# design.net
KiCad netlist of a schematic drawn in Altium Designer
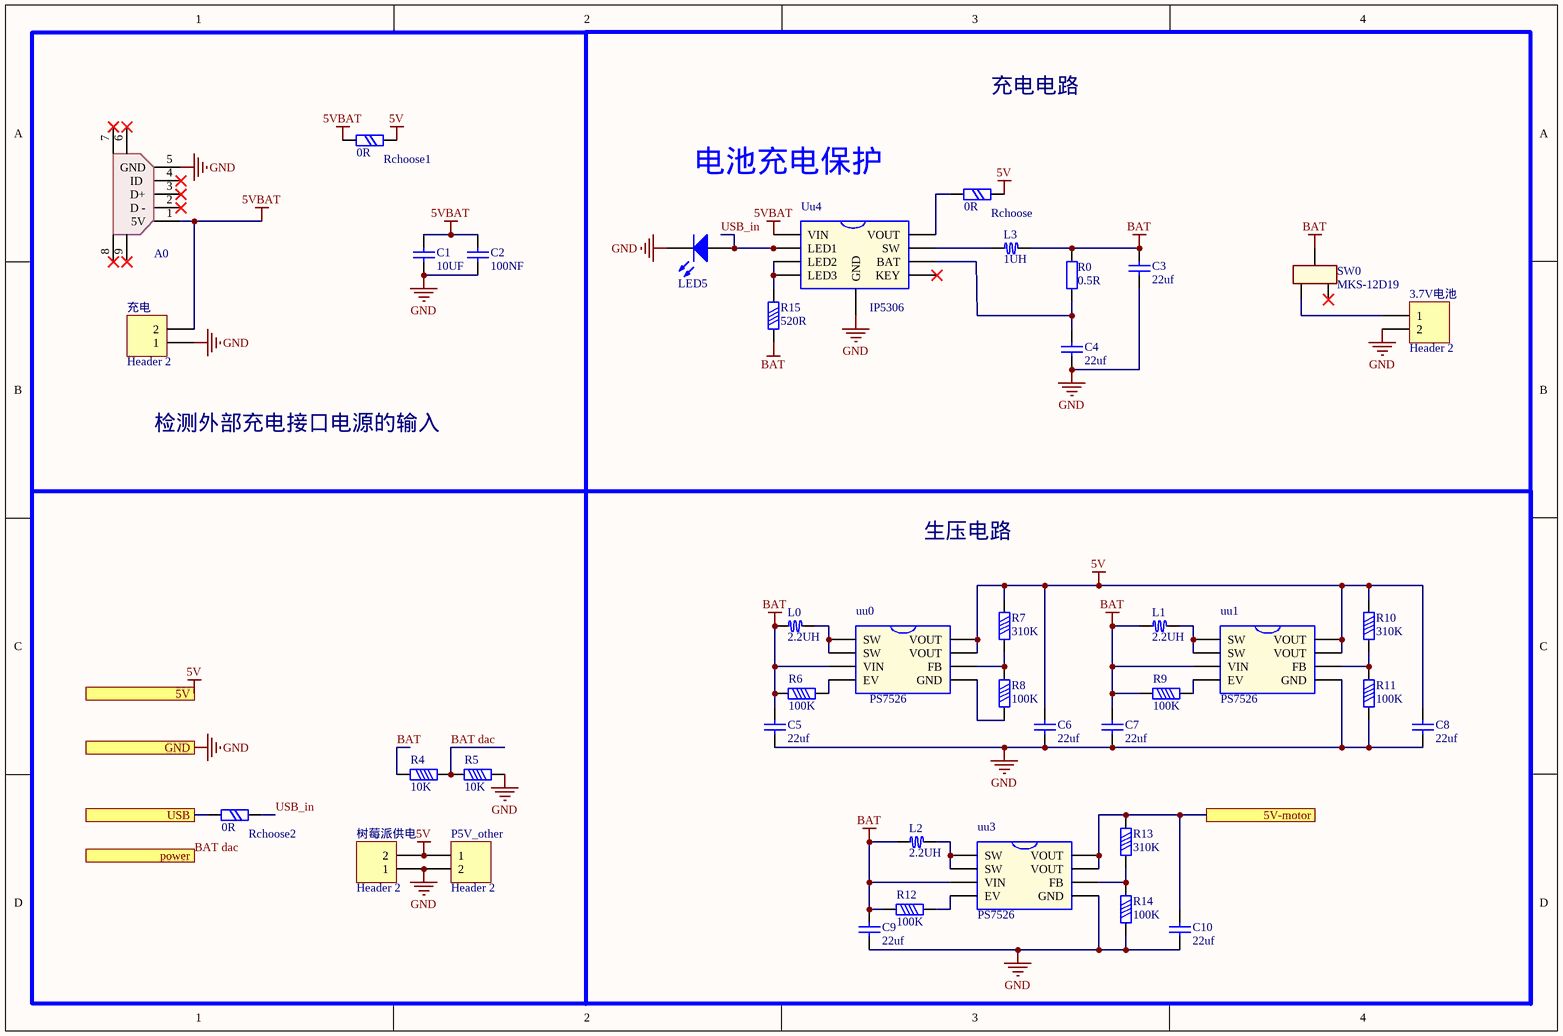
[diagram p0: 电源设计.SchDoc]

(export (version "E")
  (design (tool "Eeschema 10.0.6"))
  (components
    (comp (ref "3.7V电池")
      (value "Header 2")
      (footprint "HX2.54-2")
      (description "Header, 2-Pin")
      (fields (field (name "PUBLISHER") "Altium Limited"))
      (libsource (lib "") (part "Header 2_1"))
    )
    (comp (ref "A0")
      (value "Micro USB")
      (footprint "Micro USB")
      (libsource (lib "tianxiaohua_Schlib") (part "Micro USB"))
    )
    (comp (ref "C1")
      (value "10UF")
      (footprint "CC2012-0805")
      (description "Polarized Capacitor (Radial)")
      (fields (field (name "Comment") "Cap Chip 0805") (field (name "PUBLISHER") "Altium Limited"))
      (libsource (lib "EButterflyIntegratedLibrary") (part "Cap Chip 0805"))
    )
    (comp (ref "C2")
      (value "100NF")
      (footprint "CC2012-0805")
      (description "Polarized Capacitor (Radial)")
      (fields (field (name "Comment") "Cap Chip 0805") (field (name "PUBLISHER") "Altium Limited"))
      (libsource (lib "EButterflyIntegratedLibrary") (part "Cap Chip 0805"))
    )
    (comp (ref "C3")
      (value "22uf")
      (footprint "CC2012-0805")
      (description "Polarized Capacitor (Radial)")
      (fields (field (name "Comment") "Cap Chip 0805") (field (name "PUBLISHER") "Altium Limited"))
      (libsource (lib "EButterflyIntegratedLibrary") (part "Cap Chip 0805"))
    )
    (comp (ref "C4")
      (value "22uf")
      (footprint "CC2012-0805")
      (description "Polarized Capacitor (Radial)")
      (fields (field (name "Comment") "Cap Chip 0805") (field (name "PUBLISHER") "Altium Limited"))
      (libsource (lib "EButterflyIntegratedLibrary") (part "Cap Chip 0805"))
    )
    (comp (ref "C5")
      (value "22uf")
      (footprint "CC2012-0805")
      (description "Polarized Capacitor (Radial)")
      (fields (field (name "Comment") "Cap Chip 0805") (field (name "PUBLISHER") "Altium Limited"))
      (libsource (lib "EButterflyIntegratedLibrary") (part "Cap Chip 0805"))
    )
    (comp (ref "C6")
      (value "22uf")
      (footprint "CC2012-0805")
      (description "Polarized Capacitor (Radial)")
      (fields (field (name "Comment") "Cap Chip 0805") (field (name "PUBLISHER") "Altium Limited"))
      (libsource (lib "EButterflyIntegratedLibrary") (part "Cap Chip 0805"))
    )
    (comp (ref "C7")
      (value "22uf")
      (footprint "CC2012-0805")
      (description "Polarized Capacitor (Radial)")
      (fields (field (name "Comment") "Cap Chip 0805") (field (name "PUBLISHER") "Altium Limited"))
      (libsource (lib "EButterflyIntegratedLibrary") (part "Cap Chip 0805"))
    )
    (comp (ref "C8")
      (value "22uf")
      (footprint "CC2012-0805")
      (description "Polarized Capacitor (Radial)")
      (fields (field (name "Comment") "Cap Chip 0805") (field (name "PUBLISHER") "Altium Limited"))
      (libsource (lib "EButterflyIntegratedLibrary") (part "Cap Chip 0805"))
    )
    (comp (ref "C9")
      (value "22uf")
      (footprint "CC2012-0805")
      (description "Polarized Capacitor (Radial)")
      (fields (field (name "Comment") "Cap Chip 0805") (field (name "PUBLISHER") "Altium Limited"))
      (libsource (lib "EButterflyIntegratedLibrary") (part "Cap Chip 0805"))
    )
    (comp (ref "C10")
      (value "22uf")
      (footprint "CC2012-0805")
      (description "Polarized Capacitor (Radial)")
      (fields (field (name "Comment") "Cap Chip 0805") (field (name "PUBLISHER") "Altium Limited"))
      (libsource (lib "EButterflyIntegratedLibrary") (part "Cap Chip 0805"))
    )
    (comp (ref "L0")
      (value "2.2UH")
      (footprint "Inductor-1040")
      (description "圆柱线圈的贴片电感")
      (libsource (lib "tianxiaohua_Schlib") (part "Inductor"))
    )
    (comp (ref "L1")
      (value "2.2UH")
      (footprint "Inductor-1040")
      (description "圆柱线圈的贴片电感")
      (libsource (lib "tianxiaohua_Schlib") (part "Inductor"))
    )
    (comp (ref "L2")
      (value "2.2UH")
      (footprint "Inductor-1040")
      (description "圆柱线圈的贴片电感")
      (libsource (lib "tianxiaohua_Schlib") (part "Inductor"))
    )
    (comp (ref "L3")
      (value "1UH")
      (footprint "Inductor-1040")
      (description "圆柱线圈的贴片电感")
      (libsource (lib "tianxiaohua_Schlib") (part "Inductor"))
    )
    (comp (ref "LED5")
      (value "LED Chip")
      (footprint "CLED1608-0603")
      (description "Typical Chip LED")
      (fields (field (name "PUBLISHER") "Altium Limited"))
      (libsource (lib "EButterflyIntegratedLibrary") (part "LED Chip"))
    )
    (comp (ref "P5V_other")
      (value "Header 2")
      (footprint "HDR1X2")
      (description "Header, 2-Pin")
      (fields (field (name "PUBLISHER") "Altium Limited"))
      (libsource (lib "") (part "Header 2_1"))
    )
    (comp (ref "R0")
      (value "0.5R")
      (footprint "CR2012-0805")
      (description "Resistor")
      (fields (field (name "Comment") "Resistor Chip 0805") (field (name "PUBLISHER") "Altium Limited"))
      (libsource (lib "EButterflyIntegratedLibrary") (part "Resistor Chip 0805"))
    )
    (comp (ref "R4")
      (value "10K")
      (footprint "CR1608-0603")
      (description "Resistor")
      (fields (field (name "Comment") "Resistor Chip 0603") (field (name "PUBLISHER") "Altium Limited"))
      (libsource (lib "") (part "Resistor Chip 0603_3"))
    )
    (comp (ref "R5")
      (value "10K")
      (footprint "CR1608-0603")
      (description "Resistor")
      (fields (field (name "Comment") "Resistor Chip 0603") (field (name "PUBLISHER") "Altium Limited"))
      (libsource (lib "") (part "Resistor Chip 0603_1"))
    )
    (comp (ref "R6")
      (value "100K")
      (footprint "CR1608-0603")
      (description "Resistor")
      (fields (field (name "Comment") "Resistor Chip 0603") (field (name "PUBLISHER") "Altium Limited"))
      (libsource (lib "") (part "Resistor Chip 0603_1"))
    )
    (comp (ref "R7")
      (value "310K")
      (footprint "CR1608-0603")
      (description "Resistor")
      (fields (field (name "Comment") "Resistor Chip 0603") (field (name "PUBLISHER") "Altium Limited"))
      (libsource (lib "EButterflyIntegratedLibrary") (part "Resistor Chip 0603"))
    )
    (comp (ref "R8")
      (value "100K")
      (footprint "CR1608-0603")
      (description "Resistor")
      (fields (field (name "Comment") "Resistor Chip 0603") (field (name "PUBLISHER") "Altium Limited"))
      (libsource (lib "EButterflyIntegratedLibrary") (part "Resistor Chip 0603"))
    )
    (comp (ref "R9")
      (value "100K")
      (footprint "CR1608-0603")
      (description "Resistor")
      (fields (field (name "Comment") "Resistor Chip 0603") (field (name "PUBLISHER") "Altium Limited"))
      (libsource (lib "") (part "Resistor Chip 0603_1"))
    )
    (comp (ref "R10")
      (value "310K")
      (footprint "CR1608-0603")
      (description "Resistor")
      (fields (field (name "Comment") "Resistor Chip 0603") (field (name "PUBLISHER") "Altium Limited"))
      (libsource (lib "EButterflyIntegratedLibrary") (part "Resistor Chip 0603"))
    )
    (comp (ref "R11")
      (value "100K")
      (footprint "CR1608-0603")
      (description "Resistor")
      (fields (field (name "Comment") "Resistor Chip 0603") (field (name "PUBLISHER") "Altium Limited"))
      (libsource (lib "EButterflyIntegratedLibrary") (part "Resistor Chip 0603"))
    )
    (comp (ref "R12")
      (value "100K")
      (footprint "CR1608-0603")
      (description "Resistor")
      (fields (field (name "Comment") "Resistor Chip 0603") (field (name "PUBLISHER") "Altium Limited"))
      (libsource (lib "") (part "Resistor Chip 0603_1"))
    )
    (comp (ref "R13")
      (value "310K")
      (footprint "CR1608-0603")
      (description "Resistor")
      (fields (field (name "Comment") "Resistor Chip 0603") (field (name "PUBLISHER") "Altium Limited"))
      (libsource (lib "EButterflyIntegratedLibrary") (part "Resistor Chip 0603"))
    )
    (comp (ref "R14")
      (value "100K")
      (footprint "CR1608-0603")
      (description "Resistor")
      (fields (field (name "Comment") "Resistor Chip 0603") (field (name "PUBLISHER") "Altium Limited"))
      (libsource (lib "EButterflyIntegratedLibrary") (part "Resistor Chip 0603"))
    )
    (comp (ref "R15")
      (value "520R")
      (footprint "CR1608-0603")
      (description "Resistor")
      (fields (field (name "Comment") "Resistor Chip 0603") (field (name "PUBLISHER") "Altium Limited"))
      (libsource (lib "") (part "Resistor Chip 0603_2"))
    )
    (comp (ref "Rchoose")
      (value "0R")
      (footprint "CR3216-1206")
      (description "Resistor")
      (fields (field (name "Comment") "Resistor Chip 1206") (field (name "PUBLISHER") "Altium Limited"))
      (libsource (lib "EButterflyIntegratedLibrary") (part "Resistor Chip 1206"))
    )
    (comp (ref "Rchoose1")
      (value "0R")
      (footprint "CR3216-1206")
      (description "Resistor")
      (fields (field (name "Comment") "Resistor Chip 1206") (field (name "PUBLISHER") "Altium Limited"))
      (libsource (lib "EButterflyIntegratedLibrary") (part "Resistor Chip 1206"))
    )
    (comp (ref "Rchoose2")
      (value "0R")
      (footprint "CR3216-1206")
      (description "Resistor")
      (fields (field (name "Comment") "Resistor Chip 1206") (field (name "PUBLISHER") "Altium Limited"))
      (libsource (lib "EButterflyIntegratedLibrary") (part "Resistor Chip 1206"))
    )
    (comp (ref "SW0")
      (value "MKS-12D19")
      (footprint "SW  MKS 12D19")
      (libsource (lib "tianxiaohua_Schlib") (part "sw-MSK-12D19"))
    )
    (comp (ref "uu0")
      (value "PS7526")
      (footprint "ESOP8")
      (libsource (lib "tianxiaohua_Schlib") (part "PS7526"))
    )
    (comp (ref "uu1")
      (value "PS7526")
      (footprint "ESOP8")
      (libsource (lib "tianxiaohua_Schlib") (part "PS7526"))
    )
    (comp (ref "uu3")
      (value "PS7526")
      (footprint "ESOP8")
      (libsource (lib "tianxiaohua_Schlib") (part "PS7526"))
    )
    (comp (ref "Uu4")
      (value "IP5306")
      (footprint "ESOP8")
      (description "2A的锂电池充电ic,同时具有升压5V输出的功能")
      (libsource (lib "tianxiaohua_Schlib") (part "IP5306"))
    )
    (comp (ref "充电")
      (value "Header 2")
      (footprint "HX2.54-2")
      (description "Header, 2-Pin")
      (fields (field (name "PUBLISHER") "Altium Limited"))
      (libsource (lib "EButterflyIntegratedLibrary") (part "Header 2"))
    )
    (comp (ref "树莓派供电")
      (value "Header 2")
      (footprint "HX2.54-2")
      (description "Header, 2-Pin")
      (fields (field (name "PUBLISHER") "Altium Limited"))
      (libsource (lib "EButterflyIntegratedLibrary") (part "Header 2"))
    )
  )
  (nets
    (net (code "1") (name "/5V-motor") (class "Default")
      (node (ref "C10") (pin "1") (pinfunction "1_1") (pintype "passive"))
      (node (ref "R13") (pin "1") (pinfunction "1_1") (pintype "passive"))
      (node (ref "uu3") (pin "7") (pinfunction "VOUT_7") (pintype "passive"))
      (node (ref "uu3") (pin "8") (pinfunction "VOUT_8") (pintype "passive"))
    )
    (net (code "2") (name "/BAT dac") (class "Default")
      (node (ref "R4") (pin "1") (pinfunction "1_1") (pintype "passive"))
      (node (ref "R5") (pin "1") (pinfunction "1_1") (pintype "passive"))
    )
    (net (code "3") (name "/USB") (class "Default")
      (node (ref "Rchoose2") (pin "1") (pinfunction "1_1") (pintype "passive"))
    )
    (net (code "4") (name "/USB_in") (class "Default")
      (node (ref "LED5") (pin "1") (pinfunction "A_1") (pintype "passive"))
      (node (ref "Rchoose2") (pin "2") (pinfunction "2_2") (pintype "passive"))
      (node (ref "Uu4") (pin "2") (pinfunction "LED1_2") (pintype "passive"))
    )
    (net (code "5") (name "5V") (class "Default")
      (node (ref "C6") (pin "1") (pinfunction "1_1") (pintype "passive"))
      (node (ref "C8") (pin "1") (pinfunction "1_1") (pintype "passive"))
      (node (ref "P5V_other") (pin "1") (pinfunction "1_1") (pintype "passive"))
      (node (ref "R10") (pin "1") (pinfunction "1_1") (pintype "passive"))
      (node (ref "R7") (pin "1") (pinfunction "1_1") (pintype "passive"))
      (node (ref "Rchoose") (pin "2") (pinfunction "2_2") (pintype "passive"))
      (node (ref "Rchoose1") (pin "2") (pinfunction "2_2") (pintype "passive"))
      (node (ref "uu0") (pin "7") (pinfunction "VOUT_7") (pintype "passive"))
      (node (ref "uu0") (pin "8") (pinfunction "VOUT_8") (pintype "passive"))
      (node (ref "uu1") (pin "7") (pinfunction "VOUT_7") (pintype "passive"))
      (node (ref "uu1") (pin "8") (pinfunction "VOUT_8") (pintype "passive"))
      (node (ref "树莓派供电") (pin "2") (pinfunction "2_2") (pintype "passive"))
    )
    (net (code "6") (name "5VBAT") (class "Default")
      (node (ref "A0") (pin "1") (pinfunction "5V_1") (pintype "passive"))
      (node (ref "C1") (pin "2") (pinfunction "2_2") (pintype "passive"))
      (node (ref "C2") (pin "2") (pinfunction "2_2") (pintype "passive"))
      (node (ref "Rchoose1") (pin "1") (pinfunction "1_1") (pintype "passive"))
      (node (ref "Uu4") (pin "1") (pinfunction "VIN_1") (pintype "passive"))
      (node (ref "充电") (pin "2") (pinfunction "2_2") (pintype "passive"))
    )
    (net (code "7") (name "BAT") (class "Default")
      (node (ref "C3") (pin "1") (pinfunction "1_1") (pintype "passive"))
      (node (ref "C5") (pin "1") (pinfunction "1_1") (pintype "passive"))
      (node (ref "C7") (pin "1") (pinfunction "1_1") (pintype "passive"))
      (node (ref "C9") (pin "1") (pinfunction "1_1") (pintype "passive"))
      (node (ref "L0") (pin "1") (pinfunction "1_1") (pintype "passive"))
      (node (ref "L1") (pin "1") (pinfunction "1_1") (pintype "passive"))
      (node (ref "L2") (pin "1") (pinfunction "1_1") (pintype "passive"))
      (node (ref "L3") (pin "2") (pinfunction "2_2") (pintype "passive"))
      (node (ref "R0") (pin "1") (pinfunction "1_1") (pintype "passive"))
      (node (ref "R12") (pin "1") (pinfunction "1_1") (pintype "passive"))
      (node (ref "R15") (pin "1") (pinfunction "1_1") (pintype "passive"))
      (node (ref "R4") (pin "2") (pinfunction "2_2") (pintype "passive"))
      (node (ref "R6") (pin "1") (pinfunction "1_1") (pintype "passive"))
      (node (ref "R9") (pin "1") (pinfunction "1_1") (pintype "passive"))
      (node (ref "SW0") (pin "2") (pinfunction "2_2") (pintype "passive"))
      (node (ref "uu0") (pin "3") (pinfunction "VIN_3") (pintype "passive"))
      (node (ref "uu1") (pin "3") (pinfunction "VIN_3") (pintype "passive"))
      (node (ref "uu3") (pin "3") (pinfunction "VIN_3") (pintype "passive"))
    )
    (net (code "8") (name "GND") (class "Default")
      (node (ref "3.7V电池") (pin "2") (pinfunction "2_2") (pintype "passive"))
      (node (ref "A0") (pin "5") (pinfunction "GND_5") (pintype "passive"))
      (node (ref "C1") (pin "1") (pinfunction "1_1") (pintype "passive"))
      (node (ref "C10") (pin "2") (pinfunction "2_2") (pintype "passive"))
      (node (ref "C2") (pin "1") (pinfunction "1_1") (pintype "passive"))
      (node (ref "C3") (pin "2") (pinfunction "2_2") (pintype "passive"))
      (node (ref "C4") (pin "1") (pinfunction "1_1") (pintype "passive"))
      (node (ref "C5") (pin "2") (pinfunction "2_2") (pintype "passive"))
      (node (ref "C6") (pin "2") (pinfunction "2_2") (pintype "passive"))
      (node (ref "C7") (pin "2") (pinfunction "2_2") (pintype "passive"))
      (node (ref "C8") (pin "2") (pinfunction "2_2") (pintype "passive"))
      (node (ref "C9") (pin "2") (pinfunction "2_2") (pintype "passive"))
      (node (ref "LED5") (pin "2") (pinfunction "K_2") (pintype "passive"))
      (node (ref "P5V_other") (pin "2") (pinfunction "2_2") (pintype "passive"))
      (node (ref "R11") (pin "2") (pinfunction "2_2") (pintype "passive"))
      (node (ref "R14") (pin "2") (pinfunction "2_2") (pintype "passive"))
      (node (ref "R5") (pin "2") (pinfunction "2_2") (pintype "passive"))
      (node (ref "Uu4") (pin "9") (pinfunction "GND_9") (pintype "passive"))
      (node (ref "uu1") (pin "5") (pinfunction "GND_5") (pintype "passive"))
      (node (ref "uu3") (pin "5") (pinfunction "GND_5") (pintype "passive"))
      (node (ref "充电") (pin "1") (pinfunction "1_1") (pintype "passive"))
      (node (ref "树莓派供电") (pin "1") (pinfunction "1_1") (pintype "passive"))
    )
    (net (code "9") (name "Net-(3.7V电池-Pad1)") (class "Default")
      (node (ref "3.7V电池") (pin "1") (pinfunction "1_1") (pintype "passive"))
      (node (ref "SW0") (pin "3") (pinfunction "3_3") (pintype "passive"))
    )
    (net (code "10") (name "Net-(L0-Pad2)") (class "Default")
      (node (ref "L0") (pin "2") (pinfunction "2_2") (pintype "passive"))
      (node (ref "uu0") (pin "1") (pinfunction "SW_1") (pintype "passive"))
      (node (ref "uu0") (pin "2") (pinfunction "SW_2") (pintype "passive"))
    )
    (net (code "11") (name "Net-(L1-Pad2)") (class "Default")
      (node (ref "L1") (pin "2") (pinfunction "2_2") (pintype "passive"))
      (node (ref "uu1") (pin "1") (pinfunction "SW_1") (pintype "passive"))
      (node (ref "uu1") (pin "2") (pinfunction "SW_2") (pintype "passive"))
    )
    (net (code "12") (name "Net-(L2-Pad2)") (class "Default")
      (node (ref "L2") (pin "2") (pinfunction "2_2") (pintype "passive"))
      (node (ref "uu3") (pin "1") (pinfunction "SW_1") (pintype "passive"))
      (node (ref "uu3") (pin "2") (pinfunction "SW_2") (pintype "passive"))
    )
    (net (code "13") (name "Net-(Uu4-BAT)") (class "Default")
      (node (ref "C4") (pin "2") (pinfunction "2_2") (pintype "passive"))
      (node (ref "R0") (pin "2") (pinfunction "2_2") (pintype "passive"))
      (node (ref "Uu4") (pin "6") (pinfunction "BAT_6") (pintype "passive"))
    )
    (net (code "14") (name "Net-(Uu4-LED2)") (class "Default")
      (node (ref "R15") (pin "2") (pinfunction "2_2") (pintype "passive"))
      (node (ref "Uu4") (pin "3") (pinfunction "LED2_3") (pintype "passive"))
      (node (ref "Uu4") (pin "4") (pinfunction "LED3_4") (pintype "passive"))
    )
    (net (code "15") (name "Net-(Uu4-SW)") (class "Default")
      (node (ref "L3") (pin "1") (pinfunction "1_1") (pintype "passive"))
      (node (ref "Uu4") (pin "7") (pinfunction "SW_7") (pintype "passive"))
    )
    (net (code "16") (name "Net-(Uu4-VOUT)") (class "Default")
      (node (ref "Rchoose") (pin "1") (pinfunction "1_1") (pintype "passive"))
      (node (ref "Uu4") (pin "8") (pinfunction "VOUT_8") (pintype "passive"))
    )
    (net (code "17") (name "Net-(uu0-EV)") (class "Default")
      (node (ref "R6") (pin "2") (pinfunction "2_2") (pintype "passive"))
      (node (ref "uu0") (pin "4") (pinfunction "EV_4") (pintype "passive"))
    )
    (net (code "18") (name "Net-(uu0-FB)") (class "Default")
      (node (ref "R7") (pin "2") (pinfunction "2_2") (pintype "passive"))
      (node (ref "R8") (pin "1") (pinfunction "1_1") (pintype "passive"))
      (node (ref "uu0") (pin "6") (pinfunction "FB_6") (pintype "passive"))
    )
    (net (code "19") (name "Net-(uu0-GND)") (class "Default")
      (node (ref "R8") (pin "2") (pinfunction "2_2") (pintype "passive"))
      (node (ref "uu0") (pin "5") (pinfunction "GND_5") (pintype "passive"))
    )
    (net (code "20") (name "Net-(uu1-EV)") (class "Default")
      (node (ref "R9") (pin "2") (pinfunction "2_2") (pintype "passive"))
      (node (ref "uu1") (pin "4") (pinfunction "EV_4") (pintype "passive"))
    )
    (net (code "21") (name "Net-(uu1-FB)") (class "Default")
      (node (ref "R10") (pin "2") (pinfunction "2_2") (pintype "passive"))
      (node (ref "R11") (pin "1") (pinfunction "1_1") (pintype "passive"))
      (node (ref "uu1") (pin "6") (pinfunction "FB_6") (pintype "passive"))
    )
    (net (code "22") (name "Net-(uu3-EV)") (class "Default")
      (node (ref "R12") (pin "2") (pinfunction "2_2") (pintype "passive"))
      (node (ref "uu3") (pin "4") (pinfunction "EV_4") (pintype "passive"))
    )
    (net (code "23") (name "Net-(uu3-FB)") (class "Default")
      (node (ref "R13") (pin "2") (pinfunction "2_2") (pintype "passive"))
      (node (ref "R14") (pin "1") (pinfunction "1_1") (pintype "passive"))
      (node (ref "uu3") (pin "6") (pinfunction "FB_6") (pintype "passive"))
    )
    (net (code "24") (name "unconnected-(A0-D+-Pad3)") (class "Default")
      (node (ref "A0") (pin "3") (pinfunction "D+_3") (pintype "passive+no_connect"))
    )
    (net (code "25") (name "unconnected-(A0-D_--Pad2)") (class "Default")
      (node (ref "A0") (pin "2") (pinfunction "D_-_2") (pintype "passive+no_connect"))
    )
    (net (code "26") (name "unconnected-(A0-ID-Pad4)") (class "Default")
      (node (ref "A0") (pin "4") (pinfunction "ID_4") (pintype "passive+no_connect"))
    )
    (net (code "27") (name "unconnected-(A0-Pad6)") (class "Default")
      (node (ref "A0") (pin "6") (pinfunction "6_6") (pintype "passive+no_connect"))
    )
    (net (code "28") (name "unconnected-(A0-Pad7)") (class "Default")
      (node (ref "A0") (pin "7") (pinfunction "7_7") (pintype "passive+no_connect"))
    )
    (net (code "29") (name "unconnected-(A0-Pad8)") (class "Default")
      (node (ref "A0") (pin "8") (pinfunction "8_8") (pintype "passive+no_connect"))
    )
    (net (code "30") (name "unconnected-(A0-Pad9)") (class "Default")
      (node (ref "A0") (pin "9") (pinfunction "9_9") (pintype "passive+no_connect"))
    )
    (net (code "31") (name "unconnected-(SW0-Pad1)") (class "Default")
      (node (ref "SW0") (pin "1") (pinfunction "1_1") (pintype "passive+no_connect"))
    )
    (net (code "32") (name "unconnected-(Uu4-KEY-Pad5)") (class "Default")
      (node (ref "Uu4") (pin "5") (pinfunction "KEY_5") (pintype "passive"))
    )
  )
)
